# T18_cad.net
KiCad netlist of a schematic drawn in EAGLE
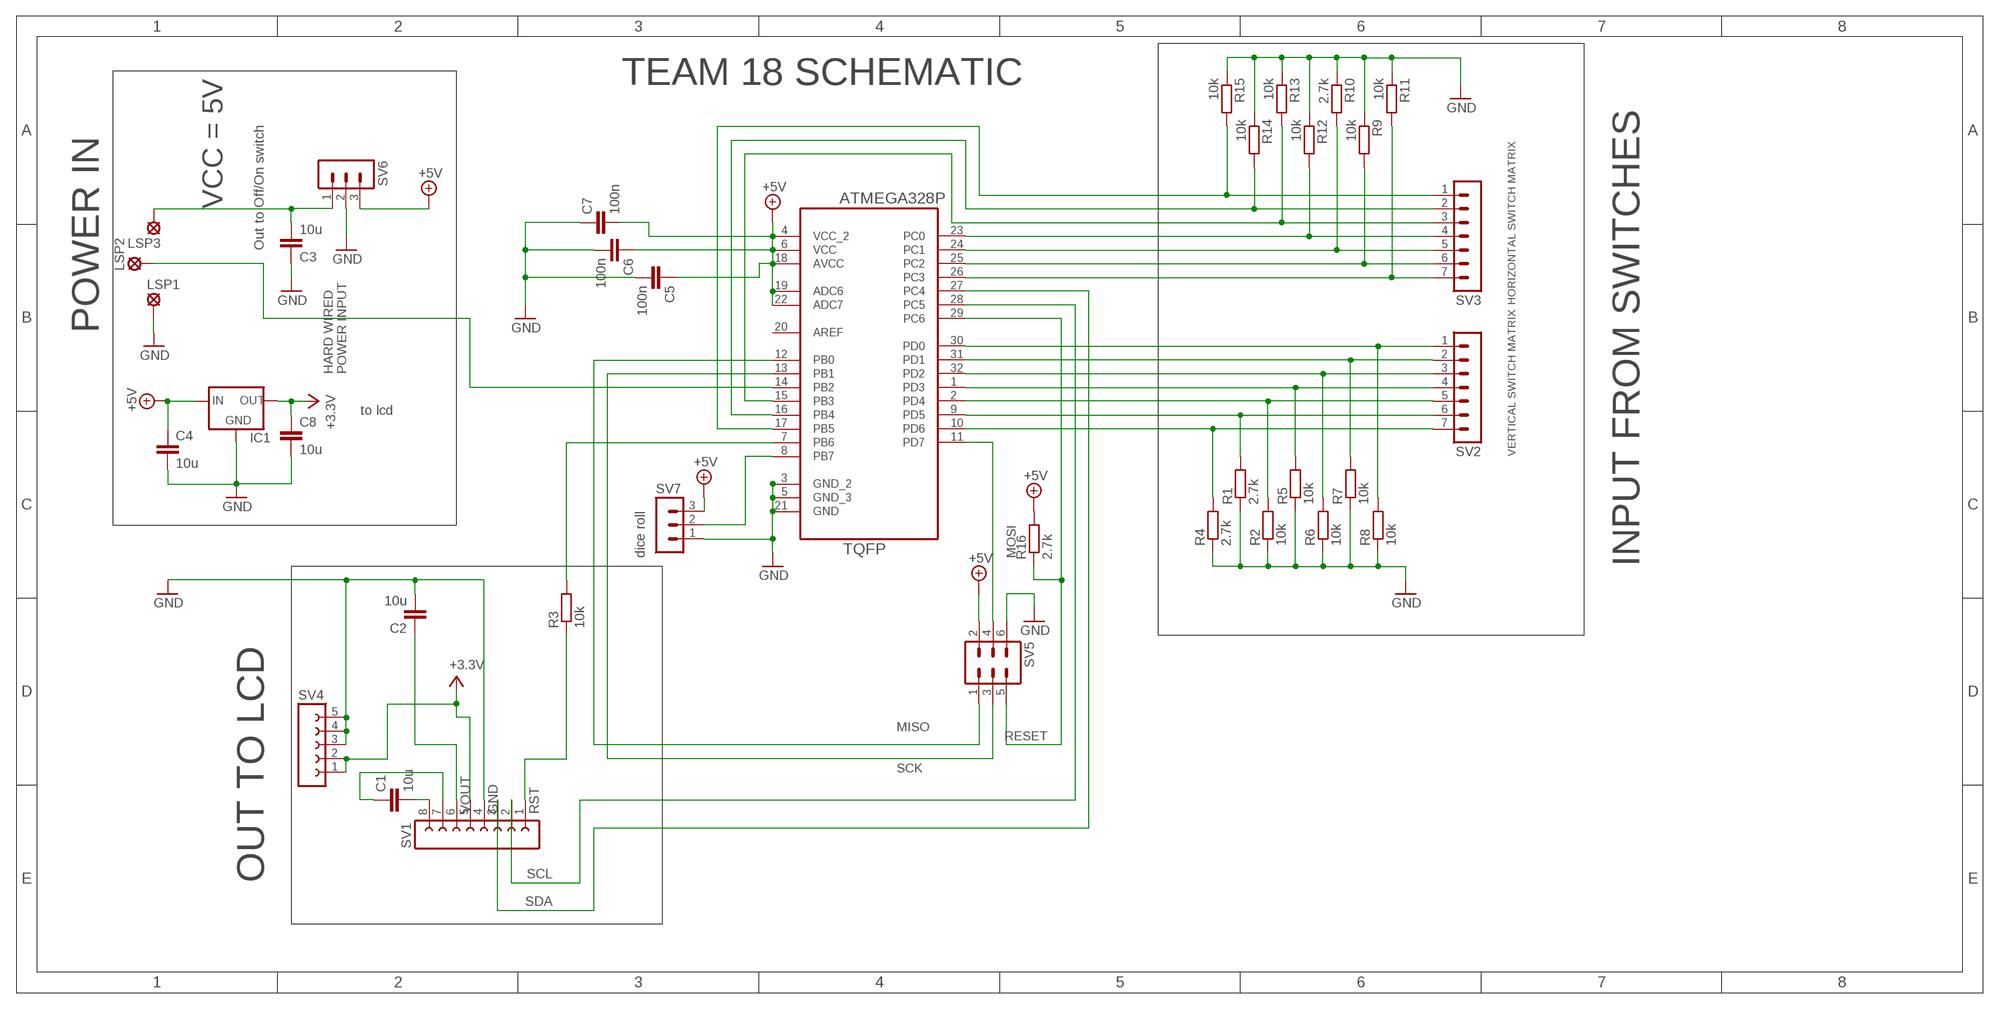
[diagram p0: schematic, sheet 1]

(export (version "E")
  (design (tool "Eeschema 10.0.6"))
  (components
    (comp (ref "C1")
      (value "10u")
      (footprint "eagle-import:C0603")
      (libsource (lib "eagle-import") (part "CC0603"))
    )
    (comp (ref "C2")
      (value "10u")
      (footprint "eagle-import:C0603")
      (libsource (lib "eagle-import") (part "CC0603"))
    )
    (comp (ref "C3")
      (value "10u")
      (footprint "eagle-import:C0603")
      (libsource (lib "eagle-import") (part "CC0603"))
    )
    (comp (ref "C4")
      (value "10u")
      (footprint "eagle-import:C0603")
      (libsource (lib "eagle-import") (part "CC0603"))
    )
    (comp (ref "C5")
      (value "100n")
      (footprint "eagle-import:C0603")
      (libsource (lib "eagle-import") (part "CC0603"))
    )
    (comp (ref "C6")
      (value "100n")
      (footprint "eagle-import:C0603")
      (libsource (lib "eagle-import") (part "CC0603"))
    )
    (comp (ref "C7")
      (value "100n")
      (footprint "eagle-import:C0603")
      (libsource (lib "eagle-import") (part "CC0603"))
    )
    (comp (ref "C8")
      (value "10u")
      (footprint "eagle-import:C0603")
      (libsource (lib "eagle-import") (part "CC0603"))
    )
    (comp (ref "IC1")
      (value "78LXX")
      (footprint "eagle-import:78LXX")
      (libsource (lib "eagle-import") (part "78LXX"))
    )
    (comp (ref "LSP1")
      (value "SE14")
      (footprint "eagle-import:SE14")
      (libsource (lib "eagle-import") (part "SE14"))
    )
    (comp (ref "LSP2")
      (value "SE14")
      (footprint "eagle-import:SE14")
      (libsource (lib "eagle-import") (part "SE14"))
    )
    (comp (ref "LSP3")
      (value "SE14")
      (footprint "eagle-import:SE14")
      (libsource (lib "eagle-import") (part "SE14"))
    )
    (comp (ref "R1")
      (value "2.7k")
      (footprint "eagle-import:R0603")
      (libsource (lib "eagle-import") (part "RR0603"))
    )
    (comp (ref "R2")
      (value "10k")
      (footprint "eagle-import:R0603")
      (libsource (lib "eagle-import") (part "RR0603"))
    )
    (comp (ref "R3")
      (value "10k")
      (footprint "eagle-import:R0603")
      (libsource (lib "eagle-import") (part "RR0603"))
    )
    (comp (ref "R4")
      (value "2.7k")
      (footprint "eagle-import:R0603")
      (libsource (lib "eagle-import") (part "RR0603"))
    )
    (comp (ref "R5")
      (value "10k")
      (footprint "eagle-import:R0603")
      (libsource (lib "eagle-import") (part "RR0603"))
    )
    (comp (ref "R6")
      (value "10k")
      (footprint "eagle-import:R0603")
      (libsource (lib "eagle-import") (part "RR0603"))
    )
    (comp (ref "R7")
      (value "10k")
      (footprint "eagle-import:R0603")
      (libsource (lib "eagle-import") (part "RR0603"))
    )
    (comp (ref "R8")
      (value "10k")
      (footprint "eagle-import:R0603")
      (libsource (lib "eagle-import") (part "RR0603"))
    )
    (comp (ref "R9")
      (value "10k")
      (footprint "eagle-import:R0603")
      (libsource (lib "eagle-import") (part "RR0603"))
    )
    (comp (ref "R10")
      (value "2.7k")
      (footprint "eagle-import:R0603")
      (libsource (lib "eagle-import") (part "RR0603"))
    )
    (comp (ref "R11")
      (value "10k")
      (footprint "eagle-import:R0603")
      (libsource (lib "eagle-import") (part "RR0603"))
    )
    (comp (ref "R12")
      (value "10k")
      (footprint "eagle-import:R0603")
      (libsource (lib "eagle-import") (part "RR0603"))
    )
    (comp (ref "R13")
      (value "10k")
      (footprint "eagle-import:R0603")
      (libsource (lib "eagle-import") (part "RR0603"))
    )
    (comp (ref "R14")
      (value "10k")
      (footprint "eagle-import:R0603")
      (libsource (lib "eagle-import") (part "RR0603"))
    )
    (comp (ref "R15")
      (value "10k")
      (footprint "eagle-import:R0603")
      (libsource (lib "eagle-import") (part "RR0603"))
    )
    (comp (ref "R16")
      (value "2.7k")
      (footprint "eagle-import:R0603")
      (libsource (lib "eagle-import") (part "RR0603"))
    )
    (comp (ref "SV1")
      (value "FE08-1")
      (footprint "eagle-import:FE08")
      (libsource (lib "eagle-import") (part "FE08-1"))
    )
    (comp (ref "SV2")
      (value "MA07-1")
      (footprint "eagle-import:MA07-1")
      (libsource (lib "eagle-import") (part "MA07-1"))
    )
    (comp (ref "SV3")
      (value "MA07-1")
      (footprint "eagle-import:MA07-1")
      (libsource (lib "eagle-import") (part "MA07-1"))
    )
    (comp (ref "SV4")
      (value "FE05-1")
      (footprint "eagle-import:FE05-1")
      (libsource (lib "eagle-import") (part "FE05-1"))
    )
    (comp (ref "SV5")
      (value "MA03-2")
      (footprint "eagle-import:MA03-2")
      (libsource (lib "eagle-import") (part "MA03-2"))
    )
    (comp (ref "SV6")
      (value "MA03-1")
      (footprint "eagle-import:MA03-1")
      (libsource (lib "eagle-import") (part "MA03-1"))
    )
    (comp (ref "SV7")
      (value "MA03-1")
      (footprint "eagle-import:MA03-1")
      (libsource (lib "eagle-import") (part "MA03-1"))
    )
    (comp (ref "U1")
      (value "ATMEGA328P-AU")
      (footprint "eagle-import:QFP80P900X900X120-32N")
      (libsource (lib "eagle-import") (part "ATMEGA328P-AU"))
    )
  )
  (nets
    (net (code "1") (name "+3.3V") (class "Default")
      (node (ref "C8") (pin "1") (pinfunction "1_1") (pintype "passive"))
      (node (ref "IC1") (pin "OUT") (pinfunction "OUT_OUT") (pintype "passive"))
      (node (ref "SV1") (pin "5") (pinfunction "5_5") (pintype "passive"))
      (node (ref "SV4") (pin "1") (pinfunction "1_1") (pintype "passive"))
      (node (ref "SV4") (pin "2") (pinfunction "2_2") (pintype "passive"))
    )
    (net (code "2") (name "+5V") (class "Default")
      (node (ref "C4") (pin "1") (pinfunction "1_1") (pintype "passive"))
      (node (ref "C5") (pin "1") (pinfunction "1_1") (pintype "passive"))
      (node (ref "C6") (pin "1") (pinfunction "1_1") (pintype "passive"))
      (node (ref "C7") (pin "2") (pinfunction "2_2") (pintype "passive"))
      (node (ref "IC1") (pin "IN") (pinfunction "IN_IN") (pintype "input"))
      (node (ref "R16") (pin "2") (pinfunction "2_2") (pintype "passive"))
      (node (ref "SV5") (pin "2") (pinfunction "2_2") (pintype "passive"))
      (node (ref "SV6") (pin "3") (pinfunction "3_3") (pintype "passive"))
      (node (ref "SV7") (pin "3") (pinfunction "3_3") (pintype "passive"))
      (node (ref "U1") (pin "18") (pinfunction "AVCC_18") (pintype "power_in"))
      (node (ref "U1") (pin "19") (pinfunction "ADC6_19") (pintype "input"))
      (node (ref "U1") (pin "22") (pinfunction "ADC7_22") (pintype "input"))
      (node (ref "U1") (pin "4") (pinfunction "VCC_2_4") (pintype "power_in"))
      (node (ref "U1") (pin "6") (pinfunction "VCC_6") (pintype "power_in"))
    )
    (net (code "3") (name "/MISO") (class "Default")
      (node (ref "SV5") (pin "1") (pinfunction "1_1") (pintype "passive"))
      (node (ref "U1") (pin "12") (pinfunction "PB0_12") (pintype "bidirectional"))
    )
    (net (code "4") (name "/MOSI") (class "Default")
      (node (ref "SV5") (pin "4") (pinfunction "4_4") (pintype "passive"))
      (node (ref "U1") (pin "11") (pinfunction "PD7_11") (pintype "bidirectional"))
    )
    (net (code "5") (name "/RESET") (class "Default")
      (node (ref "R16") (pin "1") (pinfunction "1_1") (pintype "passive"))
      (node (ref "SV5") (pin "5") (pinfunction "5_5") (pintype "passive"))
      (node (ref "U1") (pin "29") (pinfunction "PC6_29") (pintype "bidirectional"))
    )
    (net (code "6") (name "/RST") (class "Default")
      (node (ref "R3") (pin "1") (pinfunction "1_1") (pintype "passive"))
      (node (ref "SV1") (pin "1") (pinfunction "1_1") (pintype "passive"))
    )
    (net (code "7") (name "/SCK") (class "Default")
      (node (ref "SV5") (pin "3") (pinfunction "3_3") (pintype "passive"))
      (node (ref "U1") (pin "13") (pinfunction "PB1_13") (pintype "bidirectional"))
    )
    (net (code "8") (name "/SCL") (class "Default")
      (node (ref "SV1") (pin "2") (pinfunction "2_2") (pintype "passive"))
      (node (ref "U1") (pin "28") (pinfunction "PC5_28") (pintype "bidirectional"))
    )
    (net (code "9") (name "/SDA") (class "Default")
      (node (ref "SV1") (pin "3") (pinfunction "3_3") (pintype "passive"))
      (node (ref "U1") (pin "27") (pinfunction "PC4_27") (pintype "bidirectional"))
    )
    (net (code "10") (name "/VOUT") (class "Default")
      (node (ref "C2") (pin "1") (pinfunction "1_1") (pintype "passive"))
      (node (ref "SV1") (pin "6") (pinfunction "6_6") (pintype "passive"))
    )
    (net (code "11") (name "GND") (class "Default")
      (node (ref "C2") (pin "2") (pinfunction "2_2") (pintype "passive"))
      (node (ref "C3") (pin "1") (pinfunction "1_1") (pintype "passive"))
      (node (ref "C4") (pin "2") (pinfunction "2_2") (pintype "passive"))
      (node (ref "C5") (pin "2") (pinfunction "2_2") (pintype "passive"))
      (node (ref "C6") (pin "2") (pinfunction "2_2") (pintype "passive"))
      (node (ref "C7") (pin "1") (pinfunction "1_1") (pintype "passive"))
      (node (ref "C8") (pin "2") (pinfunction "2_2") (pintype "passive"))
      (node (ref "IC1") (pin "GND") (pinfunction "GND_GND") (pintype "input"))
      (node (ref "LSP1") (pin "MP") (pinfunction "MP_MP") (pintype "passive"))
      (node (ref "R1") (pin "1") (pinfunction "1_1") (pintype "passive"))
      (node (ref "R10") (pin "1") (pinfunction "1_1") (pintype "passive"))
      (node (ref "R11") (pin "1") (pinfunction "1_1") (pintype "passive"))
      (node (ref "R12") (pin "1") (pinfunction "1_1") (pintype "passive"))
      (node (ref "R13") (pin "1") (pinfunction "1_1") (pintype "passive"))
      (node (ref "R14") (pin "1") (pinfunction "1_1") (pintype "passive"))
      (node (ref "R15") (pin "1") (pinfunction "1_1") (pintype "passive"))
      (node (ref "R2") (pin "1") (pinfunction "1_1") (pintype "passive"))
      (node (ref "R4") (pin "1") (pinfunction "1_1") (pintype "passive"))
      (node (ref "R5") (pin "1") (pinfunction "1_1") (pintype "passive"))
      (node (ref "R6") (pin "1") (pinfunction "1_1") (pintype "passive"))
      (node (ref "R7") (pin "1") (pinfunction "1_1") (pintype "passive"))
      (node (ref "R8") (pin "1") (pinfunction "1_1") (pintype "passive"))
      (node (ref "R9") (pin "1") (pinfunction "1_1") (pintype "passive"))
      (node (ref "SV1") (pin "4") (pinfunction "4_4") (pintype "passive"))
      (node (ref "SV4") (pin "3") (pinfunction "3_3") (pintype "passive"))
      (node (ref "SV4") (pin "4") (pinfunction "4_4") (pintype "passive"))
      (node (ref "SV4") (pin "5") (pinfunction "5_5") (pintype "passive"))
      (node (ref "SV5") (pin "6") (pinfunction "6_6") (pintype "passive"))
      (node (ref "SV6") (pin "2") (pinfunction "2_2") (pintype "passive"))
      (node (ref "SV7") (pin "1") (pinfunction "1_1") (pintype "passive"))
      (node (ref "U1") (pin "21") (pinfunction "GND_21") (pintype "passive"))
      (node (ref "U1") (pin "3") (pinfunction "GND_2_3") (pintype "passive"))
      (node (ref "U1") (pin "5") (pinfunction "GND_3_5") (pintype "passive"))
    )
    (net (code "12") (name "Net-(C1-Pad1)") (class "Default")
      (node (ref "C1") (pin "1") (pinfunction "1_1") (pintype "passive"))
      (node (ref "SV1") (pin "7") (pinfunction "7_7") (pintype "passive"))
    )
    (net (code "13") (name "Net-(C1-Pad2)") (class "Default")
      (node (ref "C1") (pin "2") (pinfunction "2_2") (pintype "passive"))
      (node (ref "SV1") (pin "8") (pinfunction "8_8") (pintype "passive"))
    )
    (net (code "14") (name "Net-(C3-Pad2)") (class "Default")
      (node (ref "C3") (pin "2") (pinfunction "2_2") (pintype "passive"))
      (node (ref "LSP3") (pin "MP") (pinfunction "MP_MP") (pintype "passive"))
      (node (ref "SV6") (pin "1") (pinfunction "1_1") (pintype "passive"))
    )
    (net (code "15") (name "Net-(U1-PB2)") (class "Default")
      (node (ref "LSP2") (pin "MP") (pinfunction "MP_MP") (pintype "passive"))
      (node (ref "U1") (pin "14") (pinfunction "PB2_14") (pintype "bidirectional"))
    )
    (net (code "16") (name "Net-(U1-PB3)") (class "Default")
      (node (ref "R13") (pin "2") (pinfunction "2_2") (pintype "passive"))
      (node (ref "SV3") (pin "3") (pinfunction "3_3") (pintype "passive"))
      (node (ref "U1") (pin "15") (pinfunction "PB3_15") (pintype "bidirectional"))
    )
    (net (code "17") (name "Net-(U1-PB4)") (class "Default")
      (node (ref "R14") (pin "2") (pinfunction "2_2") (pintype "passive"))
      (node (ref "SV3") (pin "2") (pinfunction "2_2") (pintype "passive"))
      (node (ref "U1") (pin "16") (pinfunction "PB4_16") (pintype "bidirectional"))
    )
    (net (code "18") (name "Net-(U1-PB5)") (class "Default")
      (node (ref "R15") (pin "2") (pinfunction "2_2") (pintype "passive"))
      (node (ref "SV3") (pin "1") (pinfunction "1_1") (pintype "passive"))
      (node (ref "U1") (pin "17") (pinfunction "PB5_17") (pintype "bidirectional"))
    )
    (net (code "19") (name "Net-(U1-PB6)") (class "Default")
      (node (ref "R3") (pin "2") (pinfunction "2_2") (pintype "passive"))
      (node (ref "U1") (pin "7") (pinfunction "PB6_7") (pintype "bidirectional"))
    )
    (net (code "20") (name "Net-(U1-PB7)") (class "Default")
      (node (ref "SV7") (pin "2") (pinfunction "2_2") (pintype "passive"))
      (node (ref "U1") (pin "8") (pinfunction "PB7_8") (pintype "bidirectional"))
    )
    (net (code "21") (name "Net-(U1-PC0)") (class "Default")
      (node (ref "R12") (pin "2") (pinfunction "2_2") (pintype "passive"))
      (node (ref "SV3") (pin "4") (pinfunction "4_4") (pintype "passive"))
      (node (ref "U1") (pin "23") (pinfunction "PC0_23") (pintype "bidirectional"))
    )
    (net (code "22") (name "Net-(U1-PC1)") (class "Default")
      (node (ref "R10") (pin "2") (pinfunction "2_2") (pintype "passive"))
      (node (ref "SV3") (pin "5") (pinfunction "5_5") (pintype "passive"))
      (node (ref "U1") (pin "24") (pinfunction "PC1_24") (pintype "bidirectional"))
    )
    (net (code "23") (name "Net-(U1-PC2)") (class "Default")
      (node (ref "R9") (pin "2") (pinfunction "2_2") (pintype "passive"))
      (node (ref "SV3") (pin "6") (pinfunction "6_6") (pintype "passive"))
      (node (ref "U1") (pin "25") (pinfunction "PC2_25") (pintype "bidirectional"))
    )
    (net (code "24") (name "Net-(U1-PC3)") (class "Default")
      (node (ref "R11") (pin "2") (pinfunction "2_2") (pintype "passive"))
      (node (ref "SV3") (pin "7") (pinfunction "7_7") (pintype "passive"))
      (node (ref "U1") (pin "26") (pinfunction "PC3_26") (pintype "bidirectional"))
    )
    (net (code "25") (name "Net-(U1-PD0)") (class "Default")
      (node (ref "R8") (pin "2") (pinfunction "2_2") (pintype "passive"))
      (node (ref "SV2") (pin "1") (pinfunction "1_1") (pintype "passive"))
      (node (ref "U1") (pin "30") (pinfunction "PD0_30") (pintype "bidirectional"))
    )
    (net (code "26") (name "Net-(U1-PD1)") (class "Default")
      (node (ref "R7") (pin "2") (pinfunction "2_2") (pintype "passive"))
      (node (ref "SV2") (pin "2") (pinfunction "2_2") (pintype "passive"))
      (node (ref "U1") (pin "31") (pinfunction "PD1_31") (pintype "bidirectional"))
    )
    (net (code "27") (name "Net-(U1-PD2)") (class "Default")
      (node (ref "R6") (pin "2") (pinfunction "2_2") (pintype "passive"))
      (node (ref "SV2") (pin "3") (pinfunction "3_3") (pintype "passive"))
      (node (ref "U1") (pin "32") (pinfunction "PD2_32") (pintype "bidirectional"))
    )
    (net (code "28") (name "Net-(U1-PD3)") (class "Default")
      (node (ref "R5") (pin "2") (pinfunction "2_2") (pintype "passive"))
      (node (ref "SV2") (pin "4") (pinfunction "4_4") (pintype "passive"))
      (node (ref "U1") (pin "1") (pinfunction "PD3_1") (pintype "bidirectional"))
    )
    (net (code "29") (name "Net-(U1-PD4)") (class "Default")
      (node (ref "R2") (pin "2") (pinfunction "2_2") (pintype "passive"))
      (node (ref "SV2") (pin "5") (pinfunction "5_5") (pintype "passive"))
      (node (ref "U1") (pin "2") (pinfunction "PD4_2") (pintype "bidirectional"))
    )
    (net (code "30") (name "Net-(U1-PD5)") (class "Default")
      (node (ref "R1") (pin "2") (pinfunction "2_2") (pintype "passive"))
      (node (ref "SV2") (pin "6") (pinfunction "6_6") (pintype "passive"))
      (node (ref "U1") (pin "9") (pinfunction "PD5_9") (pintype "bidirectional"))
    )
    (net (code "31") (name "Net-(U1-PD6)") (class "Default")
      (node (ref "R4") (pin "2") (pinfunction "2_2") (pintype "passive"))
      (node (ref "SV2") (pin "7") (pinfunction "7_7") (pintype "passive"))
      (node (ref "U1") (pin "10") (pinfunction "PD6_10") (pintype "bidirectional"))
    )
    (net (code "32") (name "unconnected-(U1-AREF-Pad20)") (class "Default")
      (node (ref "U1") (pin "20") (pinfunction "AREF_20") (pintype "input"))
    )
  )
)
